# 3_RS232.net
KiCad netlist of a schematic drawn in EAGLE
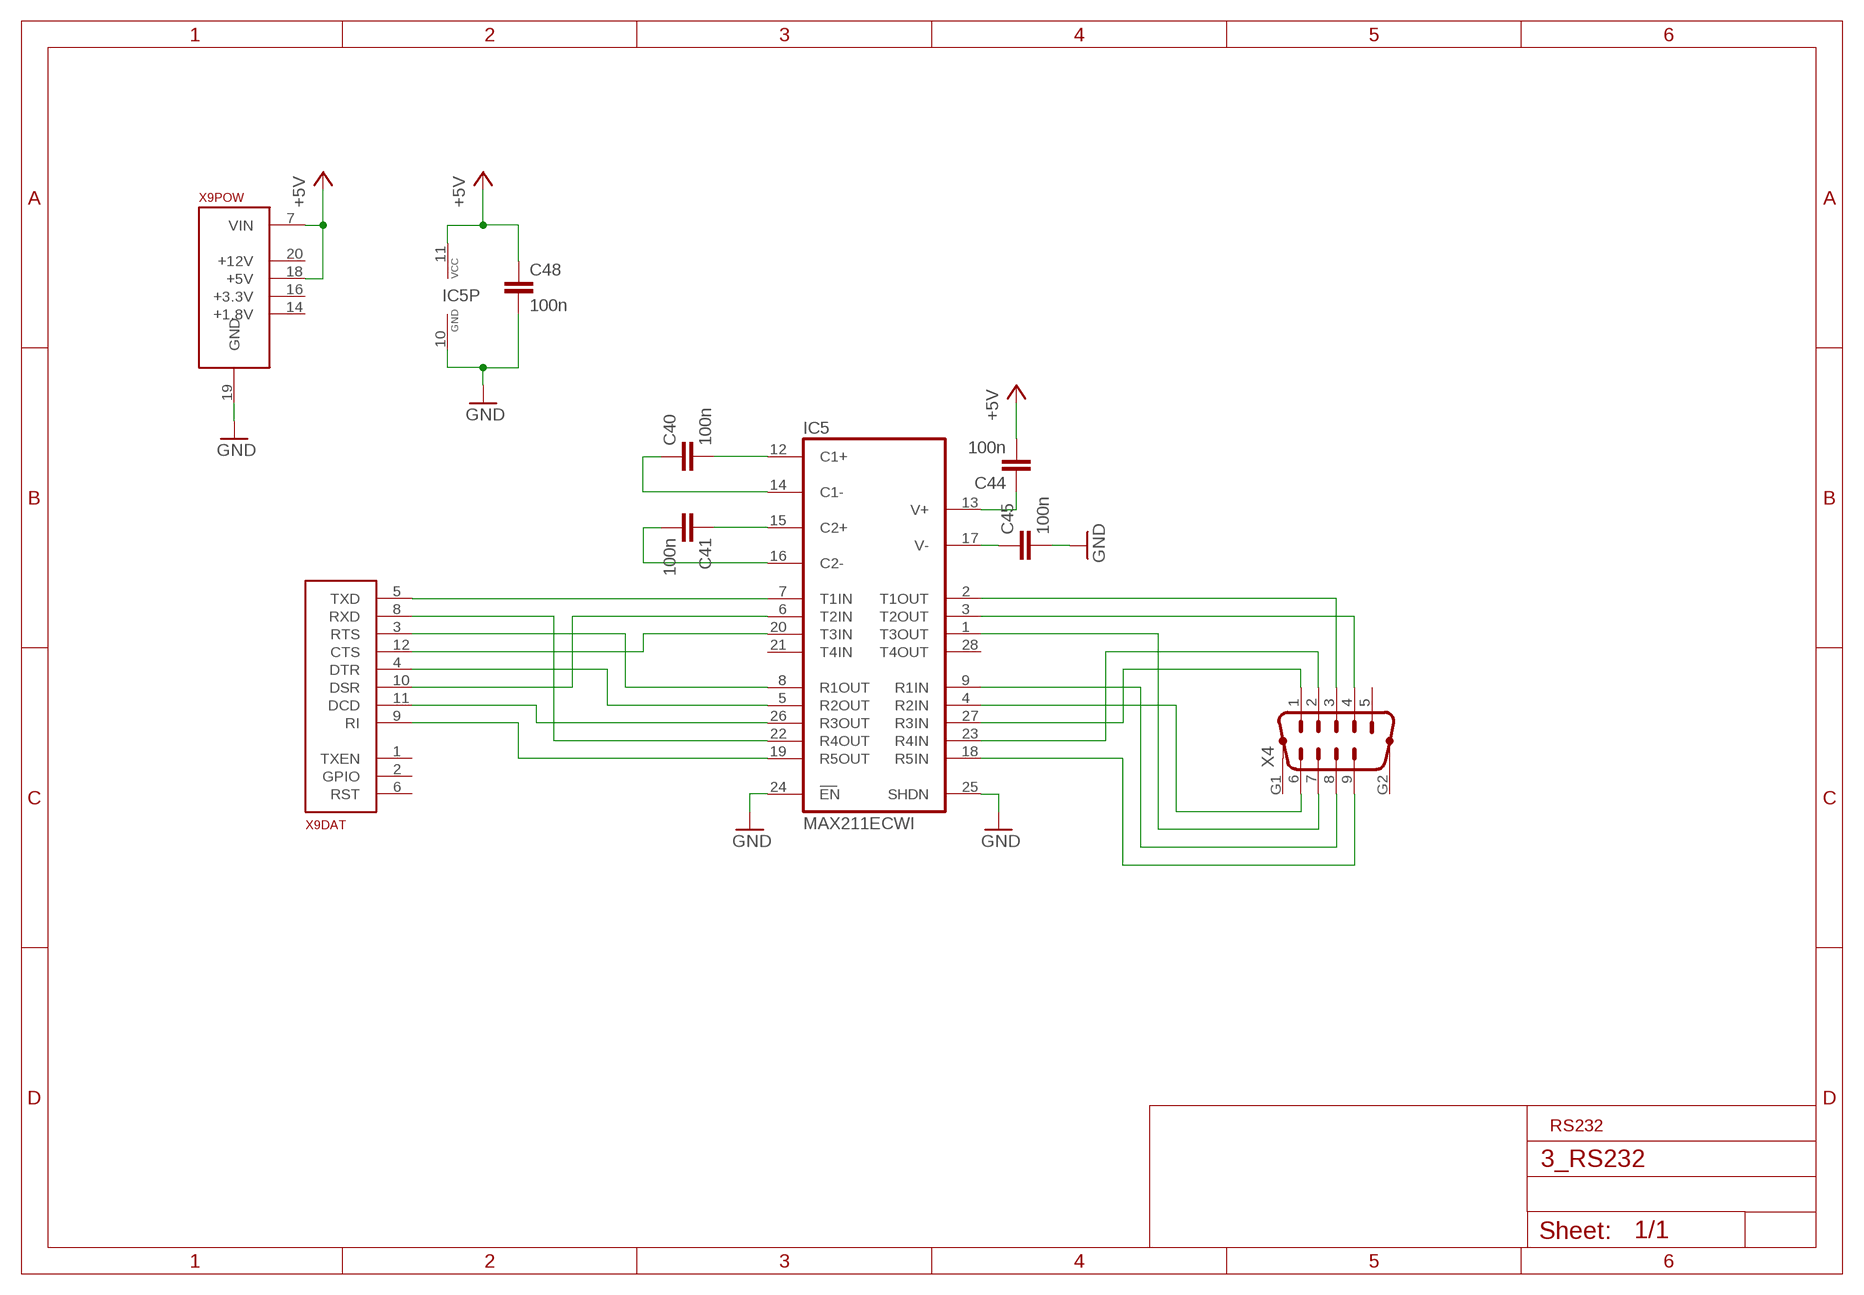
[diagram p0: schematic, sheet 1]

(export (version "E")
  (design (tool "Eeschema 10.0.6"))
  (components
    (comp (ref "C40")
      (value "100n")
      (footprint "eagle-import:C0805")
      (libsource (lib "eagle-import") (part "C-EUC0805"))
    )
    (comp (ref "C41")
      (value "100n")
      (footprint "eagle-import:C0805")
      (libsource (lib "eagle-import") (part "C-EUC0805"))
    )
    (comp (ref "C44")
      (value "100n")
      (footprint "eagle-import:C0805")
      (libsource (lib "eagle-import") (part "C-EUC0805"))
    )
    (comp (ref "C45")
      (value "100n")
      (footprint "eagle-import:C0805")
      (libsource (lib "eagle-import") (part "C-EUC0805"))
    )
    (comp (ref "C48")
      (value "100n")
      (footprint "eagle-import:C0805")
      (libsource (lib "eagle-import") (part "C-EUC0805"))
    )
    (comp (ref "IC5")
      (value "MAX211ECWI")
      (footprint "eagle-import:SO28L")
      (fields (field (name "MPN") "MAX211ECWI+T"))
      (libsource (lib "eagle-import") (part "MAX211ECWI"))
    )
    (comp (ref "X4")
      (value "M09HP")
      (footprint "eagle-import:M09HP")
      (libsource (lib "eagle-import") (part "M09HP"))
    )
    (comp (ref "X9")
      (value "ALLSERIALD")
      (footprint "eagle-import:DAUGHTER-THT")
      (libsource (lib "eagle-import") (part "ALLSERIALD"))
    )
  )
  (nets
    (net (code "1") (name "+5V") (class "Default")
      (node (ref "C44") (pin "2") (pinfunction "2_2") (pintype "passive"))
      (node (ref "C48") (pin "1") (pinfunction "1_1") (pintype "passive"))
      (node (ref "IC5") (pin "11") (pinfunction "VCC_11") (pintype "power_in"))
      (node (ref "X9") (pin "18") (pinfunction "+5V_18") (pintype "bidirectional"))
      (node (ref "X9") (pin "7") (pinfunction "VIN_7") (pintype "bidirectional"))
    )
    (net (code "2") (name "GND") (class "Default")
      (node (ref "C45") (pin "2") (pinfunction "2_2") (pintype "passive"))
      (node (ref "C48") (pin "2") (pinfunction "2_2") (pintype "passive"))
      (node (ref "IC5") (pin "10") (pinfunction "GND_10") (pintype "power_in"))
      (node (ref "IC5") (pin "24") (pinfunction "EN_24") (pintype "input"))
      (node (ref "IC5") (pin "25") (pinfunction "SHDN_25") (pintype "input"))
      (node (ref "X9") (pin "19") (pinfunction "GND_19") (pintype "bidirectional"))
    )
    (net (code "3") (name "Net-(IC5A-C1+)") (class "Default")
      (node (ref "C40") (pin "2") (pinfunction "2_2") (pintype "passive"))
      (node (ref "IC5") (pin "12") (pinfunction "C1+_12") (pintype "passive"))
    )
    (net (code "4") (name "Net-(IC5A-C1-)") (class "Default")
      (node (ref "C40") (pin "1") (pinfunction "1_1") (pintype "passive"))
      (node (ref "IC5") (pin "14") (pinfunction "C1-_14") (pintype "passive"))
    )
    (net (code "5") (name "Net-(IC5A-C2+)") (class "Default")
      (node (ref "C41") (pin "1") (pinfunction "1_1") (pintype "passive"))
      (node (ref "IC5") (pin "15") (pinfunction "C2+_15") (pintype "passive"))
    )
    (net (code "6") (name "Net-(IC5A-C2-)") (class "Default")
      (node (ref "C41") (pin "2") (pinfunction "2_2") (pintype "passive"))
      (node (ref "IC5") (pin "16") (pinfunction "C2-_16") (pintype "passive"))
    )
    (net (code "7") (name "Net-(IC5A-R1IN)") (class "Default")
      (node (ref "IC5") (pin "9") (pinfunction "R1IN_9") (pintype "input"))
      (node (ref "X4") (pin "8") (pinfunction "8_8") (pintype "passive"))
    )
    (net (code "8") (name "Net-(IC5A-R1OUT)") (class "Default")
      (node (ref "IC5") (pin "8") (pinfunction "R1OUT_8") (pintype "output"))
      (node (ref "X9") (pin "3") (pinfunction "RTS_3") (pintype "bidirectional"))
    )
    (net (code "9") (name "Net-(IC5A-R2IN)") (class "Default")
      (node (ref "IC5") (pin "4") (pinfunction "R2IN_4") (pintype "input"))
      (node (ref "X4") (pin "6") (pinfunction "6_6") (pintype "passive"))
    )
    (net (code "10") (name "Net-(IC5A-R2OUT)") (class "Default")
      (node (ref "IC5") (pin "5") (pinfunction "R2OUT_5") (pintype "output"))
      (node (ref "X9") (pin "4") (pinfunction "DTR_4") (pintype "bidirectional"))
    )
    (net (code "11") (name "Net-(IC5A-R3IN)") (class "Default")
      (node (ref "IC5") (pin "27") (pinfunction "R3IN_27") (pintype "input"))
      (node (ref "X4") (pin "1") (pinfunction "1_1") (pintype "passive"))
    )
    (net (code "12") (name "Net-(IC5A-R3OUT)") (class "Default")
      (node (ref "IC5") (pin "26") (pinfunction "R3OUT_26") (pintype "output"))
      (node (ref "X9") (pin "11") (pinfunction "DCD_11") (pintype "bidirectional"))
    )
    (net (code "13") (name "Net-(IC5A-R4IN)") (class "Default")
      (node (ref "IC5") (pin "23") (pinfunction "R4IN_23") (pintype "input"))
      (node (ref "X4") (pin "2") (pinfunction "2_2") (pintype "passive"))
    )
    (net (code "14") (name "Net-(IC5A-R4OUT)") (class "Default")
      (node (ref "IC5") (pin "22") (pinfunction "R4OUT_22") (pintype "output"))
      (node (ref "X9") (pin "8") (pinfunction "RXD_8") (pintype "bidirectional"))
    )
    (net (code "15") (name "Net-(IC5A-R5IN)") (class "Default")
      (node (ref "IC5") (pin "18") (pinfunction "R5IN_18") (pintype "input"))
      (node (ref "X4") (pin "9") (pinfunction "9_9") (pintype "passive"))
    )
    (net (code "16") (name "Net-(IC5A-R5OUT)") (class "Default")
      (node (ref "IC5") (pin "19") (pinfunction "R5OUT_19") (pintype "output"))
      (node (ref "X9") (pin "9") (pinfunction "RI_9") (pintype "bidirectional"))
    )
    (net (code "17") (name "Net-(IC5A-T1IN)") (class "Default")
      (node (ref "IC5") (pin "7") (pinfunction "T1IN_7") (pintype "input"))
      (node (ref "X9") (pin "5") (pinfunction "TXD_5") (pintype "bidirectional"))
    )
    (net (code "18") (name "Net-(IC5A-T1OUT)") (class "Default")
      (node (ref "IC5") (pin "2") (pinfunction "T1OUT_2") (pintype "output"))
      (node (ref "X4") (pin "3") (pinfunction "3_3") (pintype "passive"))
    )
    (net (code "19") (name "Net-(IC5A-T2IN)") (class "Default")
      (node (ref "IC5") (pin "6") (pinfunction "T2IN_6") (pintype "input"))
      (node (ref "X9") (pin "10") (pinfunction "DSR_10") (pintype "bidirectional"))
    )
    (net (code "20") (name "Net-(IC5A-T2OUT)") (class "Default")
      (node (ref "IC5") (pin "3") (pinfunction "T2OUT_3") (pintype "output"))
      (node (ref "X4") (pin "4") (pinfunction "4_4") (pintype "passive"))
    )
    (net (code "21") (name "Net-(IC5A-T3IN)") (class "Default")
      (node (ref "IC5") (pin "20") (pinfunction "T3IN_20") (pintype "input"))
      (node (ref "X9") (pin "12") (pinfunction "CTS_12") (pintype "bidirectional"))
    )
    (net (code "22") (name "Net-(IC5A-T3OUT)") (class "Default")
      (node (ref "IC5") (pin "1") (pinfunction "T3OUT_1") (pintype "output"))
      (node (ref "X4") (pin "7") (pinfunction "7_7") (pintype "passive"))
    )
    (net (code "23") (name "Net-(IC5A-V+)") (class "Default")
      (node (ref "C44") (pin "1") (pinfunction "1_1") (pintype "passive"))
      (node (ref "IC5") (pin "13") (pinfunction "V+_13") (pintype "passive"))
    )
    (net (code "24") (name "Net-(IC5A-V-)") (class "Default")
      (node (ref "C45") (pin "1") (pinfunction "1_1") (pintype "passive"))
      (node (ref "IC5") (pin "17") (pinfunction "V-_17") (pintype "passive"))
    )
    (net (code "25") (name "unconnected-(IC5A-T4IN-Pad21)") (class "Default")
      (node (ref "IC5") (pin "21") (pinfunction "T4IN_21") (pintype "input"))
    )
    (net (code "26") (name "unconnected-(IC5A-T4OUT-Pad28)") (class "Default")
      (node (ref "IC5") (pin "28") (pinfunction "T4OUT_28") (pintype "output"))
    )
    (net (code "27") (name "unconnected-(X4-Pad5)") (class "Default")
      (node (ref "X4") (pin "5") (pinfunction "5_5") (pintype "passive"))
    )
    (net (code "28") (name "unconnected-(X4-PadG1)") (class "Default")
      (node (ref "X4") (pin "G1") (pinfunction "G1_G1") (pintype "passive"))
    )
    (net (code "29") (name "unconnected-(X4-PadG2)") (class "Default")
      (node (ref "X4") (pin "G2") (pinfunction "G2_G2") (pintype "passive"))
    )
    (net (code "30") (name "unconnected-(X9A-GPIO-Pad2)") (class "Default")
      (node (ref "X9") (pin "2") (pinfunction "GPIO_2") (pintype "bidirectional"))
    )
    (net (code "31") (name "unconnected-(X9A-RST-Pad6)") (class "Default")
      (node (ref "X9") (pin "6") (pinfunction "RST_6") (pintype "bidirectional"))
    )
    (net (code "32") (name "unconnected-(X9A-TXEN-Pad1)") (class "Default")
      (node (ref "X9") (pin "1") (pinfunction "TXEN_1") (pintype "bidirectional"))
    )
    (net (code "33") (name "unconnected-(X9B-+1.8V-Pad14)") (class "Default")
      (node (ref "X9") (pin "14") (pinfunction "+1.8V_14") (pintype "bidirectional"))
    )
    (net (code "34") (name "unconnected-(X9B-+3.3V-Pad16)") (class "Default")
      (node (ref "X9") (pin "16") (pinfunction "+3.3V_16") (pintype "bidirectional"))
    )
    (net (code "35") (name "unconnected-(X9B-+12V-Pad20)") (class "Default")
      (node (ref "X9") (pin "20") (pinfunction "+12V_20") (pintype "bidirectional"))
    )
  )
)
